# MCU.net
KiCad netlist of a schematic drawn in Altium Designer
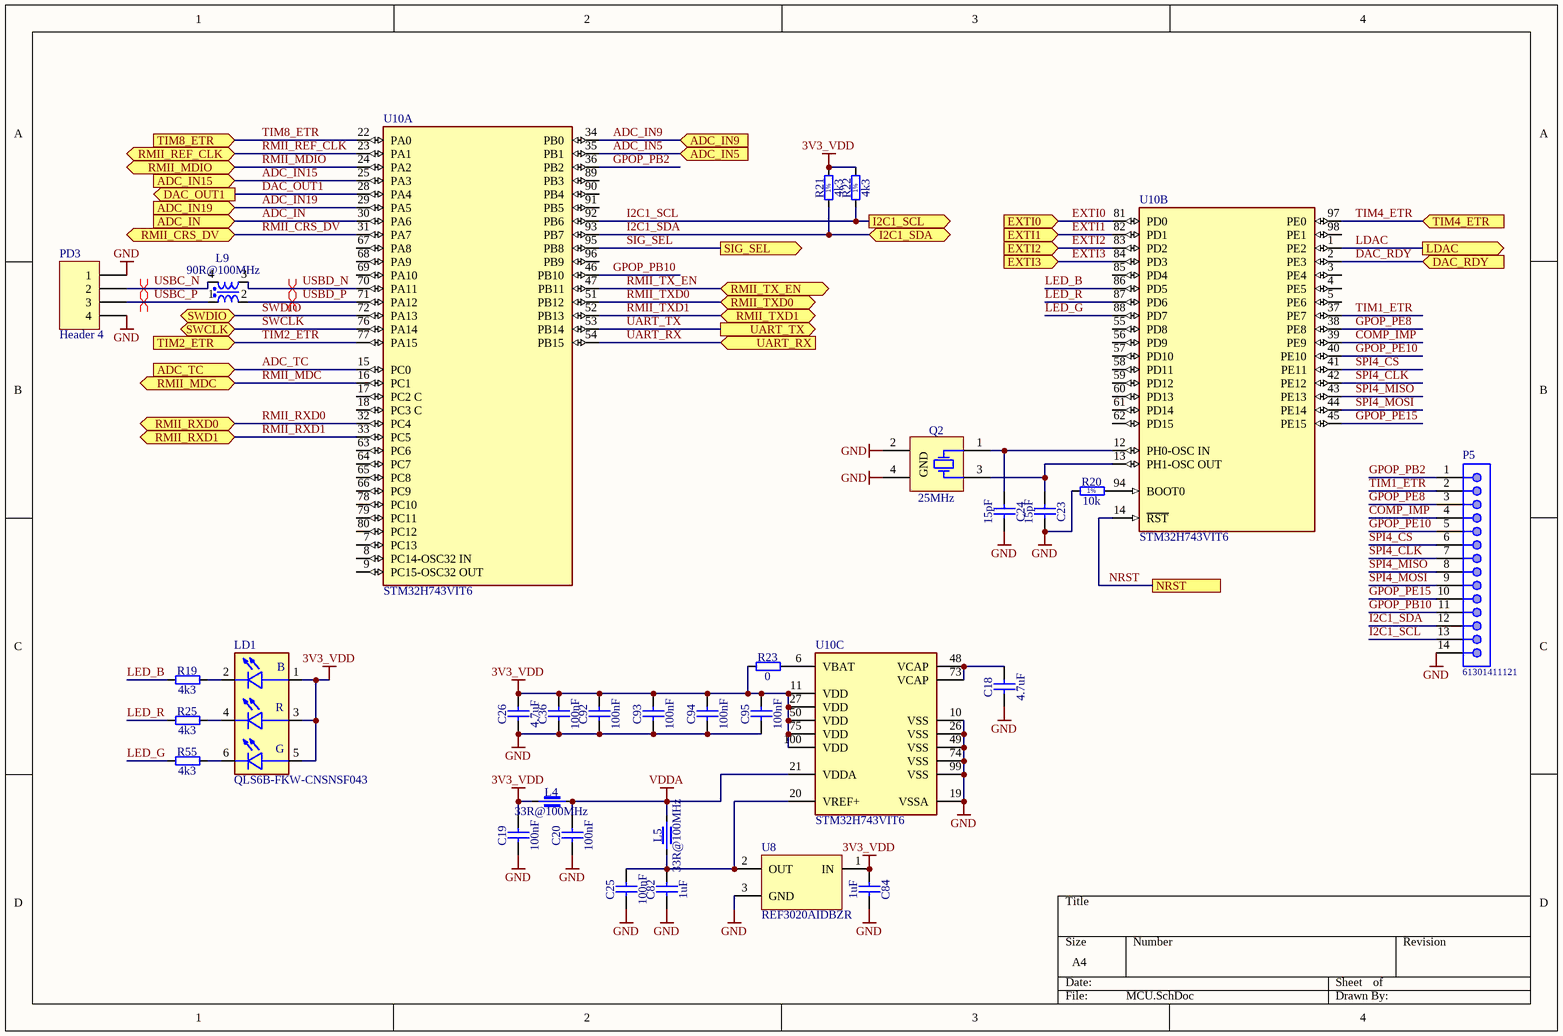
[diagram p0: MCU.SchDoc]

(export (version "E")
  (design (tool "Eeschema 10.0.6"))
  (components
    (comp (ref "C18")
      (value "4.7uF")
      (footprint "CAPC1709X95N")
      (description "Non-polarised capacitor")
      (fields
        (field (name "PART NUMBER") "CC0603_4.7UF_16V_10%_X5R")
        (field (name "VOLTAGE") "16V")
        (field (name "AUTHOR") "CERN DEM JLC")
      )
      (libsource (lib "Capacitors") (part "Capacitor - non polarized"))
    )
    (comp (ref "C19")
      (value "100nF")
      (footprint "CAPC1005X55N")
      (description "Non-polarised capacitor")
      (fields
        (field (name "PART NUMBER") "CC0402_100NF_16V_10%_X7R")
        (field (name "VOLTAGE") "16V")
        (field (name "AUTHOR") "CERN DEM JLC")
      )
      (libsource (lib "Capacitors") (part "Capacitor - non polarized"))
    )
    (comp (ref "C20")
      (value "100nF")
      (footprint "CAPC1005X55N")
      (description "Non-polarised capacitor")
      (fields
        (field (name "PART NUMBER") "CC0402_100NF_16V_10%_X7R")
        (field (name "VOLTAGE") "16V")
        (field (name "AUTHOR") "CERN DEM JLC")
      )
      (libsource (lib "Capacitors") (part "Capacitor - non polarized"))
    )
    (comp (ref "C23")
      (value "15pF")
      (footprint "CAPC1005X55N")
      (description "Non-polarised capacitor")
      (fields
        (field (name "PART NUMBER") "CC0402_15PF_50V_5%_C0G")
        (field (name "VOLTAGE") "50V")
        (field (name "AUTHOR") "CERN DEM JLC")
      )
      (libsource (lib "Capacitors") (part "Capacitor - non polarized"))
    )
    (comp (ref "C24")
      (value "15pF")
      (footprint "CAPC1005X55N")
      (description "Non-polarised capacitor")
      (fields
        (field (name "PART NUMBER") "CC0402_15PF_50V_5%_C0G")
        (field (name "VOLTAGE") "50V")
        (field (name "AUTHOR") "CERN DEM JLC")
      )
      (libsource (lib "Capacitors") (part "Capacitor - non polarized"))
    )
    (comp (ref "C25")
      (value "100nF")
      (footprint "CAPC1005X55N")
      (description "Non-polarised capacitor")
      (fields
        (field (name "PART NUMBER") "CC0402_100NF_16V_10%_X7R")
        (field (name "VOLTAGE") "16V")
        (field (name "AUTHOR") "CERN DEM JLC")
      )
      (libsource (lib "Capacitors") (part "Capacitor - non polarized"))
    )
    (comp (ref "C26")
      (value "4.7uF")
      (footprint "CAPC1709X95N")
      (description "Non-polarised capacitor")
      (fields
        (field (name "PART NUMBER") "CC0603_4.7UF_16V_10%_X5R")
        (field (name "VOLTAGE") "16V")
        (field (name "AUTHOR") "CERN DEM JLC")
      )
      (libsource (lib "Capacitors") (part "Capacitor - non polarized"))
    )
    (comp (ref "C36")
      (value "100nF")
      (footprint "CAPC1005X55N")
      (description "Non-polarised capacitor")
      (fields
        (field (name "PART NUMBER") "CC0402_100NF_16V_10%_X7R")
        (field (name "VOLTAGE") "16V")
        (field (name "AUTHOR") "CERN DEM JLC")
      )
      (libsource (lib "Capacitors") (part "Capacitor - non polarized"))
    )
    (comp (ref "C82")
      (value "1uF")
      (footprint "CAPC1005X55N")
      (description "Non-polarised capacitor")
      (fields
        (field (name "PART NUMBER") "CC0402_1UF_16V_10%_X5R")
        (field (name "VOLTAGE") "16V")
        (field (name "AUTHOR") "CERN DEM JLC")
      )
      (libsource (lib "Capacitors") (part "Capacitor - non polarized"))
    )
    (comp (ref "C84")
      (value "1uF")
      (footprint "CAPC1005X55N")
      (description "Non-polarised capacitor")
      (fields
        (field (name "PART NUMBER") "CC0402_1UF_16V_10%_X5R")
        (field (name "VOLTAGE") "16V")
        (field (name "AUTHOR") "CERN DEM JLC")
      )
      (libsource (lib "Capacitors") (part "Capacitor - non polarized"))
    )
    (comp (ref "C92")
      (value "100nF")
      (footprint "CAPC1005X55N")
      (description "Non-polarised capacitor")
      (fields
        (field (name "PART NUMBER") "CC0402_100NF_16V_10%_X7R")
        (field (name "VOLTAGE") "16V")
        (field (name "AUTHOR") "CERN DEM JLC")
      )
      (libsource (lib "Capacitors") (part "Capacitor - non polarized"))
    )
    (comp (ref "C93")
      (value "100nF")
      (footprint "CAPC1005X55N")
      (description "Non-polarised capacitor")
      (fields
        (field (name "PART NUMBER") "CC0402_100NF_16V_10%_X7R")
        (field (name "VOLTAGE") "16V")
        (field (name "AUTHOR") "CERN DEM JLC")
      )
      (libsource (lib "Capacitors") (part "Capacitor - non polarized"))
    )
    (comp (ref "C94")
      (value "100nF")
      (footprint "CAPC1005X55N")
      (description "Non-polarised capacitor")
      (fields
        (field (name "PART NUMBER") "CC0402_100NF_16V_10%_X7R")
        (field (name "VOLTAGE") "16V")
        (field (name "AUTHOR") "CERN DEM JLC")
      )
      (libsource (lib "Capacitors") (part "Capacitor - non polarized"))
    )
    (comp (ref "C95")
      (value "100nF")
      (footprint "CAPC1005X55N")
      (description "Non-polarised capacitor")
      (fields
        (field (name "PART NUMBER") "CC0402_100NF_16V_10%_X7R")
        (field (name "VOLTAGE") "16V")
        (field (name "AUTHOR") "CERN DEM JLC")
      )
      (libsource (lib "Capacitors") (part "Capacitor - non polarized"))
    )
    (comp (ref "L4")
      (value "33R@100MHz")
      (footprint "INDC1005X55N")
      (fields
        (field (name "PART NUMBER") "IND0402_MURATA_BLM15PX330SN1D")
        (field (name "POWER") "3A")
        (field (name "TOLERANCE") "±25%")
        (field (name "AUTHOR") "CERN DEM JMW")
      )
      (libsource (lib "") (part "Ferrite Bead_1"))
    )
    (comp (ref "L5")
      (value "33R@100MHz")
      (footprint "INDC1005X55N")
      (fields
        (field (name "PART NUMBER") "IND0402_MURATA_BLM15PX330SN1D")
        (field (name "POWER") "3A")
        (field (name "TOLERANCE") "±25%")
        (field (name "AUTHOR") "CERN DEM JMW")
      )
      (libsource (lib "Inductors & Transformers") (part "Ferrite Bead"))
    )
    (comp (ref "L9")
      (value "90R@100MHz")
      (footprint "IND_MURATA_DLW21S")
      (description "Inductor Common Mode")
      (fields
        (field (name "PART NUMBER") "IND_MURATA_DLW21SN900SQ2L")
        (field (name "POWER") "330mA")
        (field (name "AUTHOR") "CERN DEM JLC")
      )
      (libsource (lib "Inductors & Transformers") (part "Inductor Common Mode 1Dot-2 4Dot-3"))
    )
    (comp (ref "LD1")
      (value "QLS6B-FKW-CNSNSF043")
      (footprint "LED_QLS6B-FKW-CNSNSF043")
      (fields (field (name "MF") "Cree Inc."))
      (libsource (lib "QLS6B-FKW-CNSNSF043") (part "QLS6B-FKW-CNSNSF043"))
    )
    (comp (ref "P5")
      (value "61301411121")
      (footprint "61301411121")
      (description "WR-PHD Pin Header, THT, pitch 2.54mm, Single Row, Vertical, 14p")
      (fields (field (name "MANUFACTURER") "Wurth Elektronik"))
      (libsource (lib "Altium_WR-PHD (rev20a)") (part "61301411121"))
    )
    (comp (ref "PD3")
      (value "Header 4")
      (footprint "HDR1X4")
      (description "Header, 4-Pin")
      (fields (field (name "PUBLISHER") "Altium Limited"))
      (libsource (lib "Miscellaneous Connectors") (part "Header 4"))
    )
    (comp (ref "Q2")
      (value "25MHz")
      (footprint "XTAL_EPSON_TSX-3225")
      (description "Crystal 4 pins 1=XTAL Control 2=GND3=XTAL 4=GND")
      (fields
        (field (name "PART NUMBER") "XTAL_25MHZ_EPSON_TSX-3225 25.0000MF10Z-AC")
        (field (name "MANUFACTURER") "EPSON")
        (field (name "AUTHOR") "CERN DEM JLC")
      )
      (libsource (lib "ICs And Semiconductors") (part "Quartz Crystal 1X 2GND 3X 4GND"))
    )
    (comp (ref "R19")
      (value "4k3")
      (footprint "RESC1005X40N")
      (description "Resistor - 1%")
      (fields
        (field (name "PART NUMBER") "R0402_4K3_1%_0.0625W_100PPM")
        (field (name "POWER") "0.0625W")
        (field (name "AUTHOR") "CERN DEM JLC")
      )
      (libsource (lib "Resistors") (part "Resistor - 1%"))
    )
    (comp (ref "R20")
      (value "10k")
      (footprint "RESC1005X40N")
      (description "Resistor - 1%")
      (fields
        (field (name "PART NUMBER") "R0402_10K_1%_0.0625W_100PPM")
        (field (name "POWER") "0.0625W")
        (field (name "AUTHOR") "CERN DEM JLC")
      )
      (libsource (lib "Resistors") (part "Resistor - 1%"))
    )
    (comp (ref "R21")
      (value "4k3")
      (footprint "RESC1005X40N")
      (description "Resistor - 1%")
      (fields
        (field (name "PART NUMBER") "R0402_4K3_1%_0.0625W_100PPM")
        (field (name "POWER") "0.0625W")
        (field (name "AUTHOR") "CERN DEM JLC")
      )
      (libsource (lib "Resistors") (part "Resistor - 1%"))
    )
    (comp (ref "R22")
      (value "4k3")
      (footprint "RESC1005X40N")
      (description "Resistor - 1%")
      (fields
        (field (name "PART NUMBER") "R0402_4K3_1%_0.0625W_100PPM")
        (field (name "POWER") "0.0625W")
        (field (name "AUTHOR") "CERN DEM JLC")
      )
      (libsource (lib "Resistors") (part "Resistor - 1%"))
    )
    (comp (ref "R23")
      (value "0")
      (footprint "RESC1005X40N")
      (description "Resistor")
      (fields
        (field (name "PART NUMBER") "R0402_0R_JUMPER")
        (field (name "MANUFACTURER") "GENERIC")
        (field (name "AUTHOR") "CERN DEM JLC")
      )
      (libsource (lib "Resistors") (part "Resistor"))
    )
    (comp (ref "R25")
      (value "4k3")
      (footprint "RESC1005X40N")
      (description "Resistor - 1%")
      (fields
        (field (name "PART NUMBER") "R0402_4K3_1%_0.0625W_100PPM")
        (field (name "POWER") "0.0625W")
        (field (name "AUTHOR") "CERN DEM JLC")
      )
      (libsource (lib "Resistors") (part "Resistor - 1%"))
    )
    (comp (ref "R55")
      (value "4k3")
      (footprint "RESC1005X40N")
      (description "Resistor - 1%")
      (fields
        (field (name "PART NUMBER") "R0402_4K3_1%_0.0625W_100PPM")
        (field (name "POWER") "0.0625W")
        (field (name "AUTHOR") "CERN DEM JLC")
      )
      (libsource (lib "Resistors") (part "Resistor - 1%"))
    )
    (comp (ref "U8")
      (value "REF3020AIDBZR")
      (footprint "DBZ0003A_L")
      (fields (field (name "MANUFACTURER") "Texas Instruments"))
      (libsource (lib "Altium Content Vault") (part "TI-REF3020DBZ3"))
    )
    (comp (ref "U10")
      (value "STM32H743VIT6")
      (footprint "FP-LQFP100-1L-MFG")
      (description "IC MCU 32BIT 2MB FLASH 100LQFP")
      (fields
        (field (name "OCTOPART") "https://octopart.com/stm32h743vit6-stmicroelectronics-76372527")
        (field (name "MANUFACTURER") "STMicroelectronics")
      )
      (libsource (lib "Altium Content Vault") (part "01082ce2885d1d16a22823c45526fe6"))
    )
  )
  (nets
    (net (code "1") (name "/ADC_IN") (class "Default")
      (node (ref "U10") (pin "30") (pinfunction "PA6_30") (pintype "bidirectional"))
    )
    (net (code "2") (name "/ADC_IN5") (class "Default")
      (node (ref "U10") (pin "35") (pinfunction "PB1_35") (pintype "bidirectional"))
    )
    (net (code "3") (name "/ADC_IN9") (class "Default")
      (node (ref "U10") (pin "34") (pinfunction "PB0_34") (pintype "bidirectional"))
    )
    (net (code "4") (name "/ADC_IN15") (class "Default")
      (node (ref "U10") (pin "25") (pinfunction "PA3_25") (pintype "bidirectional"))
    )
    (net (code "5") (name "/ADC_IN19") (class "Default")
      (node (ref "U10") (pin "29") (pinfunction "PA5_29") (pintype "bidirectional"))
    )
    (net (code "6") (name "/ADC_TC") (class "Default")
      (node (ref "U10") (pin "15") (pinfunction "PC0_15") (pintype "bidirectional"))
    )
    (net (code "7") (name "/COMP_IMP") (class "Default")
      (node (ref "P5") (pin "4") (pinfunction "4_4") (pintype "passive"))
      (node (ref "U10") (pin "39") (pinfunction "PE9_39") (pintype "bidirectional"))
    )
    (net (code "8") (name "/DAC_OUT1") (class "Default")
      (node (ref "U10") (pin "28") (pinfunction "PA4_28") (pintype "bidirectional"))
    )
    (net (code "9") (name "/DAC_RDY") (class "Default")
      (node (ref "U10") (pin "2") (pinfunction "PE3_2") (pintype "bidirectional"))
    )
    (net (code "10") (name "/EXTI0") (class "Default")
      (node (ref "U10") (pin "81") (pinfunction "PD0_81") (pintype "bidirectional"))
    )
    (net (code "11") (name "/EXTI1") (class "Default")
      (node (ref "U10") (pin "82") (pinfunction "PD1_82") (pintype "bidirectional"))
    )
    (net (code "12") (name "/EXTI2") (class "Default")
      (node (ref "U10") (pin "83") (pinfunction "PD2_83") (pintype "bidirectional"))
    )
    (net (code "13") (name "/EXTI3") (class "Default")
      (node (ref "U10") (pin "84") (pinfunction "PD3_84") (pintype "bidirectional"))
    )
    (net (code "14") (name "/GPOP_PB2") (class "Default")
      (node (ref "P5") (pin "1") (pinfunction "1_1") (pintype "passive"))
      (node (ref "U10") (pin "36") (pinfunction "PB2_36") (pintype "bidirectional"))
    )
    (net (code "15") (name "/GPOP_PB10") (class "Default")
      (node (ref "P5") (pin "11") (pinfunction "11_11") (pintype "passive"))
      (node (ref "U10") (pin "46") (pinfunction "PB10_46") (pintype "bidirectional"))
    )
    (net (code "16") (name "/GPOP_PE8") (class "Default")
      (node (ref "P5") (pin "3") (pinfunction "3_3") (pintype "passive"))
      (node (ref "U10") (pin "38") (pinfunction "PE8_38") (pintype "bidirectional"))
    )
    (net (code "17") (name "/GPOP_PE10") (class "Default")
      (node (ref "P5") (pin "5") (pinfunction "5_5") (pintype "passive"))
      (node (ref "U10") (pin "40") (pinfunction "PE10_40") (pintype "bidirectional"))
    )
    (net (code "18") (name "/GPOP_PE15") (class "Default")
      (node (ref "P5") (pin "10") (pinfunction "10_10") (pintype "passive"))
      (node (ref "U10") (pin "45") (pinfunction "PE15_45") (pintype "bidirectional"))
    )
    (net (code "19") (name "/I2C1_SCL") (class "Default")
      (node (ref "P5") (pin "13") (pinfunction "13_13") (pintype "passive"))
      (node (ref "R22") (pin "1") (pinfunction "1_1") (pintype "passive"))
      (node (ref "U10") (pin "92") (pinfunction "PB6_92") (pintype "bidirectional"))
    )
    (net (code "20") (name "/I2C1_SDA") (class "Default")
      (node (ref "P5") (pin "12") (pinfunction "12_12") (pintype "passive"))
      (node (ref "R21") (pin "1") (pinfunction "1_1") (pintype "passive"))
      (node (ref "U10") (pin "93") (pinfunction "PB7_93") (pintype "bidirectional"))
    )
    (net (code "21") (name "/LDAC") (class "Default")
      (node (ref "U10") (pin "1") (pinfunction "PE2_1") (pintype "bidirectional"))
    )
    (net (code "22") (name "/LED_B") (class "Default")
      (node (ref "R19") (pin "1") (pinfunction "1_1") (pintype "passive"))
      (node (ref "U10") (pin "86") (pinfunction "PD5_86") (pintype "bidirectional"))
    )
    (net (code "23") (name "/LED_G") (class "Default")
      (node (ref "R55") (pin "1") (pinfunction "1_1") (pintype "passive"))
      (node (ref "U10") (pin "88") (pinfunction "PD7_88") (pintype "bidirectional"))
    )
    (net (code "24") (name "/LED_R") (class "Default")
      (node (ref "R25") (pin "1") (pinfunction "1_1") (pintype "passive"))
      (node (ref "U10") (pin "87") (pinfunction "PD6_87") (pintype "bidirectional"))
    )
    (net (code "25") (name "/NRST") (class "Default")
      (node (ref "U10") (pin "14") (pinfunction "~{RST}_14") (pintype "input"))
    )
    (net (code "26") (name "/RMII_CRS_DV") (class "Default")
      (node (ref "U10") (pin "31") (pinfunction "PA7_31") (pintype "bidirectional"))
    )
    (net (code "27") (name "/RMII_MDC") (class "Default")
      (node (ref "U10") (pin "16") (pinfunction "PC1_16") (pintype "bidirectional"))
    )
    (net (code "28") (name "/RMII_MDIO") (class "Default")
      (node (ref "U10") (pin "24") (pinfunction "PA2_24") (pintype "bidirectional"))
    )
    (net (code "29") (name "/RMII_REF_CLK") (class "Default")
      (node (ref "U10") (pin "23") (pinfunction "PA1_23") (pintype "bidirectional"))
    )
    (net (code "30") (name "/RMII_RXD0") (class "Default")
      (node (ref "U10") (pin "32") (pinfunction "PC4_32") (pintype "bidirectional"))
    )
    (net (code "31") (name "/RMII_RXD1") (class "Default")
      (node (ref "U10") (pin "33") (pinfunction "PC5_33") (pintype "bidirectional"))
    )
    (net (code "32") (name "/RMII_TXD0") (class "Default")
      (node (ref "U10") (pin "51") (pinfunction "PB12_51") (pintype "bidirectional"))
    )
    (net (code "33") (name "/RMII_TXD1") (class "Default")
      (node (ref "U10") (pin "52") (pinfunction "PB13_52") (pintype "bidirectional"))
    )
    (net (code "34") (name "/RMII_TX_EN") (class "Default")
      (node (ref "U10") (pin "47") (pinfunction "PB11_47") (pintype "bidirectional"))
    )
    (net (code "35") (name "/SIG_SEL") (class "Default")
      (node (ref "U10") (pin "95") (pinfunction "PB8_95") (pintype "bidirectional"))
    )
    (net (code "36") (name "/SPI4_CLK") (class "Default")
      (node (ref "P5") (pin "7") (pinfunction "7_7") (pintype "passive"))
      (node (ref "U10") (pin "42") (pinfunction "PE12_42") (pintype "bidirectional"))
    )
    (net (code "37") (name "/SPI4_CS") (class "Default")
      (node (ref "P5") (pin "6") (pinfunction "6_6") (pintype "passive"))
      (node (ref "U10") (pin "41") (pinfunction "PE11_41") (pintype "bidirectional"))
    )
    (net (code "38") (name "/SPI4_MISO") (class "Default")
      (node (ref "P5") (pin "8") (pinfunction "8_8") (pintype "passive"))
      (node (ref "U10") (pin "43") (pinfunction "PE13_43") (pintype "bidirectional"))
    )
    (net (code "39") (name "/SPI4_MOSI") (class "Default")
      (node (ref "P5") (pin "9") (pinfunction "9_9") (pintype "passive"))
      (node (ref "U10") (pin "44") (pinfunction "PE14_44") (pintype "bidirectional"))
    )
    (net (code "40") (name "/SWCLK") (class "Default")
      (node (ref "U10") (pin "76") (pinfunction "PA14_76") (pintype "bidirectional"))
    )
    (net (code "41") (name "/SWDIO") (class "Default")
      (node (ref "U10") (pin "72") (pinfunction "PA13_72") (pintype "bidirectional"))
    )
    (net (code "42") (name "/TIM1_ETR") (class "Default")
      (node (ref "P5") (pin "2") (pinfunction "2_2") (pintype "passive"))
      (node (ref "U10") (pin "37") (pinfunction "PE7_37") (pintype "bidirectional"))
    )
    (net (code "43") (name "/TIM2_ETR") (class "Default")
      (node (ref "U10") (pin "77") (pinfunction "PA15_77") (pintype "bidirectional"))
    )
    (net (code "44") (name "/TIM4_ETR") (class "Default")
      (node (ref "U10") (pin "97") (pinfunction "PE0_97") (pintype "bidirectional"))
    )
    (net (code "45") (name "/TIM8_ETR") (class "Default")
      (node (ref "U10") (pin "22") (pinfunction "PA0_22") (pintype "bidirectional"))
    )
    (net (code "46") (name "/UART_RX") (class "Default")
      (node (ref "U10") (pin "54") (pinfunction "PB15_54") (pintype "bidirectional"))
    )
    (net (code "47") (name "/UART_TX") (class "Default")
      (node (ref "U10") (pin "53") (pinfunction "PB14_53") (pintype "bidirectional"))
    )
    (net (code "48") (name "/USBC_N") (class "Default")
      (node (ref "L9") (pin "4") (pinfunction "4_4") (pintype "passive"))
      (node (ref "PD3") (pin "2") (pinfunction "2_2") (pintype "passive"))
    )
    (net (code "49") (name "/USBC_P") (class "Default")
      (node (ref "L9") (pin "1") (pinfunction "1_1") (pintype "passive"))
      (node (ref "PD3") (pin "3") (pinfunction "3_3") (pintype "passive"))
    )
    (net (code "50") (name "/USBD_N") (class "Default")
      (node (ref "L9") (pin "3") (pinfunction "3_3") (pintype "passive"))
      (node (ref "U10") (pin "70") (pinfunction "PA11_70") (pintype "bidirectional"))
    )
    (net (code "51") (name "/USBD_P") (class "Default")
      (node (ref "L9") (pin "2") (pinfunction "2_2") (pintype "passive"))
      (node (ref "U10") (pin "71") (pinfunction "PA12_71") (pintype "bidirectional"))
    )
    (net (code "52") (name "3V3_VDD") (class "Default")
      (node (ref "C19") (pin "2") (pinfunction "2_2") (pintype "passive"))
      (node (ref "C26") (pin "2") (pinfunction "2_2") (pintype "passive"))
      (node (ref "C36") (pin "2") (pinfunction "2_2") (pintype "passive"))
      (node (ref "C84") (pin "2") (pinfunction "2_2") (pintype "passive"))
      (node (ref "C92") (pin "2") (pinfunction "2_2") (pintype "passive"))
      (node (ref "C93") (pin "2") (pinfunction "2_2") (pintype "passive"))
      (node (ref "C94") (pin "2") (pinfunction "2_2") (pintype "passive"))
      (node (ref "C95") (pin "2") (pinfunction "2_2") (pintype "passive"))
      (node (ref "L4") (pin "1") (pinfunction "1_1") (pintype "passive"))
      (node (ref "LD1") (pin "1") (pinfunction "BLUE_ANODE_1") (pintype "passive"))
      (node (ref "LD1") (pin "3") (pinfunction "RED_ANODE_3") (pintype "passive"))
      (node (ref "LD1") (pin "5") (pinfunction "GREEN_ANODE_5") (pintype "passive"))
      (node (ref "R21") (pin "2") (pinfunction "2_2") (pintype "passive"))
      (node (ref "R22") (pin "2") (pinfunction "2_2") (pintype "passive"))
      (node (ref "R23") (pin "1") (pinfunction "1_1") (pintype "passive"))
      (node (ref "U10") (pin "100") (pinfunction "VDD_100") (pintype "power_in"))
      (node (ref "U10") (pin "11") (pinfunction "VDD_11") (pintype "power_in"))
      (node (ref "U10") (pin "27") (pinfunction "VDD_27") (pintype "power_in"))
      (node (ref "U10") (pin "50") (pinfunction "VDD_50") (pintype "power_in"))
      (node (ref "U10") (pin "75") (pinfunction "VDD_75") (pintype "power_in"))
      (node (ref "U8") (pin "1") (pinfunction "IN_1") (pintype "power_in"))
    )
    (net (code "53") (name "GND") (class "Default")
      (node (ref "C18") (pin "1") (pinfunction "1_1") (pintype "passive"))
      (node (ref "C19") (pin "1") (pinfunction "1_1") (pintype "passive"))
      (node (ref "C20") (pin "1") (pinfunction "1_1") (pintype "passive"))
      (node (ref "C23") (pin "1") (pinfunction "1_1") (pintype "passive"))
      (node (ref "C24") (pin "1") (pinfunction "1_1") (pintype "passive"))
      (node (ref "C25") (pin "1") (pinfunction "1_1") (pintype "passive"))
      (node (ref "C26") (pin "1") (pinfunction "1_1") (pintype "passive"))
      (node (ref "C36") (pin "1") (pinfunction "1_1") (pintype "passive"))
      (node (ref "C82") (pin "1") (pinfunction "1_1") (pintype "passive"))
      (node (ref "C84") (pin "1") (pinfunction "1_1") (pintype "passive"))
      (node (ref "C92") (pin "1") (pinfunction "1_1") (pintype "passive"))
      (node (ref "C93") (pin "1") (pinfunction "1_1") (pintype "passive"))
      (node (ref "C94") (pin "1") (pinfunction "1_1") (pintype "passive"))
      (node (ref "C95") (pin "1") (pinfunction "1_1") (pintype "passive"))
      (node (ref "P5") (pin "14") (pinfunction "14_14") (pintype "passive"))
      (node (ref "PD3") (pin "1") (pinfunction "1_1") (pintype "passive"))
      (node (ref "PD3") (pin "4") (pinfunction "4_4") (pintype "passive"))
      (node (ref "Q2") (pin "2") (pinfunction "GND_2") (pintype "power_in"))
      (node (ref "Q2") (pin "4") (pinfunction "GND_4") (pintype "power_in"))
      (node (ref "R20") (pin "1") (pinfunction "1_1") (pintype "passive"))
      (node (ref "U10") (pin "10") (pinfunction "VSS_10") (pintype "power_in"))
      (node (ref "U10") (pin "19") (pinfunction "VSSA_19") (pintype "power_in"))
      (node (ref "U10") (pin "26") (pinfunction "VSS_26") (pintype "power_in"))
      (node (ref "U10") (pin "49") (pinfunction "VSS_49") (pintype "power_in"))
      (node (ref "U10") (pin "74") (pinfunction "VSS_74") (pintype "power_in"))
      (node (ref "U10") (pin "99") (pinfunction "VSS_99") (pintype "power_in"))
      (node (ref "U8") (pin "3") (pinfunction "GND_3") (pintype "power_in"))
    )
    (net (code "54") (name "Net-(C18-Pad2)") (class "Default")
      (node (ref "C18") (pin "2") (pinfunction "2_2") (pintype "passive"))
      (node (ref "U10") (pin "48") (pinfunction "VCAP_48") (pintype "passive"))
      (node (ref "U10") (pin "73") (pinfunction "VCAP_73") (pintype "passive"))
    )
    (net (code "55") (name "Net-(LD1-BLUE_CATHODE)") (class "Default")
      (node (ref "LD1") (pin "2") (pinfunction "BLUE_CATHODE_2") (pintype "passive"))
      (node (ref "R19") (pin "2") (pinfunction "2_2") (pintype "passive"))
    )
    (net (code "56") (name "Net-(LD1-GREEN_CATHODE)") (class "Default")
      (node (ref "LD1") (pin "6") (pinfunction "GREEN_CATHODE_6") (pintype "passive"))
      (node (ref "R55") (pin "2") (pinfunction "2_2") (pintype "passive"))
    )
    (net (code "57") (name "Net-(LD1-RED_CATHODE)") (class "Default")
      (node (ref "LD1") (pin "4") (pinfunction "RED_CATHODE_4") (pintype "passive"))
      (node (ref "R25") (pin "2") (pinfunction "2_2") (pintype "passive"))
    )
    (net (code "58") (name "Net-(U10B-BOOT0)") (class "Default")
      (node (ref "R20") (pin "2") (pinfunction "2_2") (pintype "passive"))
      (node (ref "U10") (pin "94") (pinfunction "BOOT0_94") (pintype "input"))
    )
    (net (code "59") (name "Net-(U10B-PH0-OSC_IN)") (class "Default")
      (node (ref "C24") (pin "2") (pinfunction "2_2") (pintype "passive"))
      (node (ref "Q2") (pin "1") (pinfunction "X_1") (pintype "passive"))
      (node (ref "U10") (pin "12") (pinfunction "PH0-OSC_IN_12") (pintype "bidirectional"))
    )
    (net (code "60") (name "Net-(U10B-PH1-OSC_OUT)") (class "Default")
      (node (ref "C23") (pin "2") (pinfunction "2_2") (pintype "passive"))
      (node (ref "Q2") (pin "3") (pinfunction "X_3") (pintype "passive"))
      (node (ref "U10") (pin "13") (pinfunction "PH1-OSC_OUT_13") (pintype "bidirectional"))
    )
    (net (code "61") (name "Net-(U10C-VBAT)") (class "Default")
      (node (ref "R23") (pin "2") (pinfunction "2_2") (pintype "passive"))
      (node (ref "U10") (pin "6") (pinfunction "VBAT_6") (pintype "power_in"))
    )
    (net (code "62") (name "Net-(U10C-VREF+)") (class "Default")
      (node (ref "C25") (pin "2") (pinfunction "2_2") (pintype "passive"))
      (node (ref "C82") (pin "2") (pinfunction "2_2") (pintype "passive"))
      (node (ref "L5") (pin "1") (pinfunction "1_1") (pintype "passive"))
      (node (ref "U10") (pin "20") (pinfunction "VREF+_20") (pintype "power_in"))
      (node (ref "U8") (pin "2") (pinfunction "OUT_2") (pintype "power_in"))
    )
    (net (code "63") (name "VDDA") (class "Default")
      (node (ref "C20") (pin "2") (pinfunction "2_2") (pintype "passive"))
      (node (ref "L4") (pin "2") (pinfunction "2_2") (pintype "passive"))
      (node (ref "L5") (pin "2") (pinfunction "2_2") (pintype "passive"))
      (node (ref "U10") (pin "21") (pinfunction "VDDA_21") (pintype "power_in"))
    )
    (net (code "64") (name "unconnected-(U10A-PA8-Pad67)") (class "Default")
      (node (ref "U10") (pin "67") (pinfunction "PA8_67") (pintype "bidirectional"))
    )
    (net (code "65") (name "unconnected-(U10A-PA9-Pad68)") (class "Default")
      (node (ref "U10") (pin "68") (pinfunction "PA9_68") (pintype "bidirectional"))
    )
    (net (code "66") (name "unconnected-(U10A-PA10-Pad69)") (class "Default")
      (node (ref "U10") (pin "69") (pinfunction "PA10_69") (pintype "bidirectional"))
    )
    (net (code "67") (name "unconnected-(U10A-PB3-Pad89)") (class "Default")
      (node (ref "U10") (pin "89") (pinfunction "PB3_89") (pintype "bidirectional"))
    )
    (net (code "68") (name "unconnected-(U10A-PB4-Pad90)") (class "Default")
      (node (ref "U10") (pin "90") (pinfunction "PB4_90") (pintype "bidirectional"))
    )
    (net (code "69") (name "unconnected-(U10A-PB5-Pad91)") (class "Default")
      (node (ref "U10") (pin "91") (pinfunction "PB5_91") (pintype "bidirectional"))
    )
    (net (code "70") (name "unconnected-(U10A-PB9-Pad96)") (class "Default")
      (node (ref "U10") (pin "96") (pinfunction "PB9_96") (pintype "bidirectional"))
    )
    (net (code "71") (name "unconnected-(U10A-PC2_C-Pad17)") (class "Default")
      (node (ref "U10") (pin "17") (pinfunction "PC2_C_17") (pintype "bidirectional"))
    )
    (net (code "72") (name "unconnected-(U10A-PC3_C-Pad18)") (class "Default")
      (node (ref "U10") (pin "18") (pinfunction "PC3_C_18") (pintype "bidirectional"))
    )
    (net (code "73") (name "unconnected-(U10A-PC6-Pad63)") (class "Default")
      (node (ref "U10") (pin "63") (pinfunction "PC6_63") (pintype "bidirectional"))
    )
    (net (code "74") (name "unconnected-(U10A-PC7-Pad64)") (class "Default")
      (node (ref "U10") (pin "64") (pinfunction "PC7_64") (pintype "bidirectional"))
    )
    (net (code "75") (name "unconnected-(U10A-PC8-Pad65)") (class "Default")
      (node (ref "U10") (pin "65") (pinfunction "PC8_65") (pintype "bidirectional"))
    )
    (net (code "76") (name "unconnected-(U10A-PC9-Pad66)") (class "Default")
      (node (ref "U10") (pin "66") (pinfunction "PC9_66") (pintype "bidirectional"))
    )
    (net (code "77") (name "unconnected-(U10A-PC10-Pad78)") (class "Default")
      (node (ref "U10") (pin "78") (pinfunction "PC10_78") (pintype "bidirectional"))
    )
    (net (code "78") (name "unconnected-(U10A-PC11-Pad79)") (class "Default")
      (node (ref "U10") (pin "79") (pinfunction "PC11_79") (pintype "bidirectional"))
    )
    (net (code "79") (name "unconnected-(U10A-PC12-Pad80)") (class "Default")
      (node (ref "U10") (pin "80") (pinfunction "PC12_80") (pintype "bidirectional"))
    )
    (net (code "80") (name "unconnected-(U10A-PC13-Pad7)") (class "Default")
      (node (ref "U10") (pin "7") (pinfunction "PC13_7") (pintype "bidirectional"))
    )
    (net (code "81") (name "unconnected-(U10A-PC14-OSC32_IN-Pad8)") (class "Default")
      (node (ref "U10") (pin "8") (pinfunction "PC14-OSC32_IN_8") (pintype "bidirectional"))
    )
    (net (code "82") (name "unconnected-(U10A-PC15-OSC32_OUT-Pad9)") (class "Default")
      (node (ref "U10") (pin "9") (pinfunction "PC15-OSC32_OUT_9") (pintype "bidirectional"))
    )
    (net (code "83") (name "unconnected-(U10B-PD4-Pad85)") (class "Default")
      (node (ref "U10") (pin "85") (pinfunction "PD4_85") (pintype "bidirectional"))
    )
    (net (code "84") (name "unconnected-(U10B-PD8-Pad55)") (class "Default")
      (node (ref "U10") (pin "55") (pinfunction "PD8_55") (pintype "bidirectional"))
    )
    (net (code "85") (name "unconnected-(U10B-PD9-Pad56)") (class "Default")
      (node (ref "U10") (pin "56") (pinfunction "PD9_56") (pintype "bidirectional"))
    )
    (net (code "86") (name "unconnected-(U10B-PD10-Pad57)") (class "Default")
      (node (ref "U10") (pin "57") (pinfunction "PD10_57") (pintype "bidirectional"))
    )
    (net (code "87") (name "unconnected-(U10B-PD11-Pad58)") (class "Default")
      (node (ref "U10") (pin "58") (pinfunction "PD11_58") (pintype "bidirectional"))
    )
    (net (code "88") (name "unconnected-(U10B-PD12-Pad59)") (class "Default")
      (node (ref "U10") (pin "59") (pinfunction "PD12_59") (pintype "bidirectional"))
    )
    (net (code "89") (name "unconnected-(U10B-PD13-Pad60)") (class "Default")
      (node (ref "U10") (pin "60") (pinfunction "PD13_60") (pintype "bidirectional"))
    )
    (net (code "90") (name "unconnected-(U10B-PD14-Pad61)") (class "Default")
      (node (ref "U10") (pin "61") (pinfunction "PD14_61") (pintype "bidirectional"))
    )
    (net (code "91") (name "unconnected-(U10B-PD15-Pad62)") (class "Default")
      (node (ref "U10") (pin "62") (pinfunction "PD15_62") (pintype "bidirectional"))
    )
    (net (code "92") (name "unconnected-(U10B-PE1-Pad98)") (class "Default")
      (node (ref "U10") (pin "98") (pinfunction "PE1_98") (pintype "bidirectional"))
    )
    (net (code "93") (name "unconnected-(U10B-PE4-Pad3)") (class "Default")
      (node (ref "U10") (pin "3") (pinfunction "PE4_3") (pintype "bidirectional"))
    )
    (net (code "94") (name "unconnected-(U10B-PE5-Pad4)") (class "Default")
      (node (ref "U10") (pin "4") (pinfunction "PE5_4") (pintype "bidirectional"))
    )
    (net (code "95") (name "unconnected-(U10B-PE6-Pad5)") (class "Default")
      (node (ref "U10") (pin "5") (pinfunction "PE6_5") (pintype "bidirectional"))
    )
  )
)
